# Keypad.net
KiCad netlist of a schematic drawn in Altium Designer
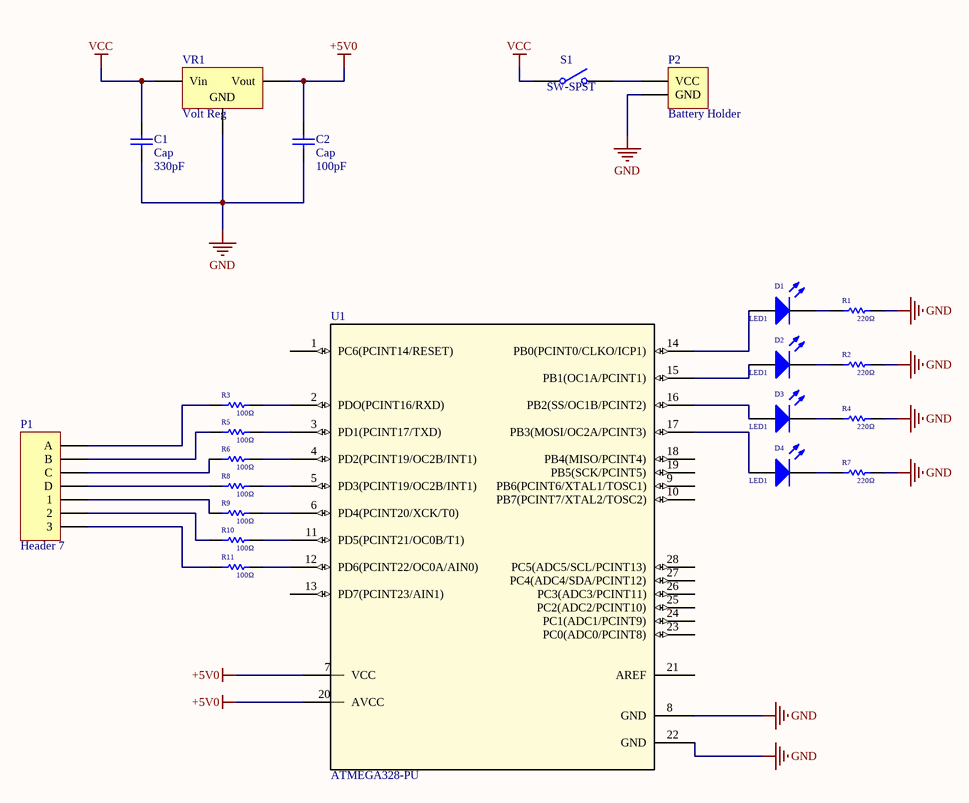
[diagram p0: Keypad.SchDoc]

(export (version "E")
  (design (tool "Eeschema 10.0.6"))
  (components
    (comp (ref "C1")
      (value "Cap")
      (footprint "RAD-0.3")
      (description "Capacitor")
      (fields (field (name "ALTIUM_VALUE") "330pF") (field (name "PUBLISHER") "Altium Limited"))
      (libsource (lib "Miscellaneous Devices") (part "Cap"))
    )
    (comp (ref "C2")
      (value "Cap")
      (footprint "RAD-0.3")
      (description "Capacitor")
      (fields (field (name "ALTIUM_VALUE") "100pF") (field (name "PUBLISHER") "Altium Limited"))
      (libsource (lib "Miscellaneous Devices") (part "Cap"))
    )
    (comp (ref "D1")
      (value "LED1")
      (footprint "LED-1")
      (description "Typical RED GaAs LED")
      (fields (field (name "PUBLISHER") "Altium Limited"))
      (libsource (lib "Miscellaneous Devices") (part "LED1"))
    )
    (comp (ref "D2")
      (value "LED1")
      (footprint "LED-1")
      (description "Typical RED GaAs LED")
      (fields (field (name "PUBLISHER") "Altium Limited"))
      (libsource (lib "Miscellaneous Devices") (part "LED1"))
    )
    (comp (ref "D3")
      (value "LED1")
      (footprint "LED-1")
      (description "Typical RED GaAs LED")
      (fields (field (name "PUBLISHER") "Altium Limited"))
      (libsource (lib "Miscellaneous Devices") (part "LED1"))
    )
    (comp (ref "D4")
      (value "LED1")
      (footprint "LED-1")
      (description "Typical RED GaAs LED")
      (fields (field (name "PUBLISHER") "Altium Limited"))
      (libsource (lib "Miscellaneous Devices") (part "LED1"))
    )
    (comp (ref "P1")
      (value "Header 7")
      (footprint "HDR1X7")
      (description "Header, 7-Pin")
      (fields (field (name "PUBLISHER") "Altium Limited"))
      (libsource (lib "Miscellaneous Connectors") (part "Header 7"))
    )
    (comp (ref "P2")
      (value "Battery Holder")
      (footprint "HDR1X2")
      (description "Header, 2-Pin")
      (fields (field (name "PUBLISHER") "Altium Limited"))
      (libsource (lib "Miscellaneous Connectors") (part "Header 2"))
    )
    (comp (ref "R1")
      (value "220Ω")
      (footprint "AXIAL-0.3")
      (description "Resistor")
      (fields (field (name "PUBLISHER") "Altium Limited"))
      (libsource (lib "Miscellaneous Devices") (part "Res1"))
    )
    (comp (ref "R2")
      (value "220Ω")
      (footprint "AXIAL-0.3")
      (description "Resistor")
      (fields (field (name "PUBLISHER") "Altium Limited"))
      (libsource (lib "Miscellaneous Devices") (part "Res1"))
    )
    (comp (ref "R3")
      (value "100Ω")
      (footprint "AXIAL-0.3")
      (description "Resistor")
      (fields (field (name "PUBLISHER") "Altium Limited"))
      (libsource (lib "Miscellaneous Devices") (part "Res1"))
    )
    (comp (ref "R4")
      (value "220Ω")
      (footprint "AXIAL-0.3")
      (description "Resistor")
      (fields (field (name "PUBLISHER") "Altium Limited"))
      (libsource (lib "Miscellaneous Devices") (part "Res1"))
    )
    (comp (ref "R5")
      (value "100Ω")
      (footprint "AXIAL-0.3")
      (description "Resistor")
      (fields (field (name "PUBLISHER") "Altium Limited"))
      (libsource (lib "Miscellaneous Devices") (part "Res1"))
    )
    (comp (ref "R6")
      (value "100Ω")
      (footprint "AXIAL-0.3")
      (description "Resistor")
      (fields (field (name "PUBLISHER") "Altium Limited"))
      (libsource (lib "Miscellaneous Devices") (part "Res1"))
    )
    (comp (ref "R7")
      (value "220Ω")
      (footprint "AXIAL-0.3")
      (description "Resistor")
      (fields (field (name "PUBLISHER") "Altium Limited"))
      (libsource (lib "Miscellaneous Devices") (part "Res1"))
    )
    (comp (ref "R8")
      (value "100Ω")
      (footprint "AXIAL-0.3")
      (description "Resistor")
      (fields (field (name "PUBLISHER") "Altium Limited"))
      (libsource (lib "Miscellaneous Devices") (part "Res1"))
    )
    (comp (ref "R9")
      (value "100Ω")
      (footprint "AXIAL-0.3")
      (description "Resistor")
      (fields (field (name "PUBLISHER") "Altium Limited"))
      (libsource (lib "Miscellaneous Devices") (part "Res1"))
    )
    (comp (ref "R10")
      (value "100Ω")
      (footprint "AXIAL-0.3")
      (description "Resistor")
      (fields (field (name "PUBLISHER") "Altium Limited"))
      (libsource (lib "Miscellaneous Devices") (part "Res1"))
    )
    (comp (ref "R11")
      (value "100Ω")
      (footprint "AXIAL-0.3")
      (description "Resistor")
      (fields (field (name "PUBLISHER") "Altium Limited"))
      (libsource (lib "Miscellaneous Devices") (part "Res1"))
    )
    (comp (ref "S1")
      (value "SW-SPST")
      (footprint "SPST-2")
      (description "Single-Pole, Single-Throw Switch")
      (fields (field (name "PUBLISHER") "Altium Limited"))
      (libsource (lib "Miscellaneous Devices") (part "SW-SPST"))
    )
    (comp (ref "U1")
      (value "ATMEGA328-PU")
      (footprint "28P3_SPDIP28_SP_MCH")
      (description "No Description Available")
      (fields (field (name "COPYRIGHT") "Copyright (C) 2018 Accelerated Designs. All rights reserved"))
      (libsource (lib "2021-05-22_12-07-40") (part "ATMEGA328-PU"))
    )
    (comp (ref "VR1")
      (value "Volt Reg")
      (footprint "D2PAK_N")
      (description "Voltage Regulator")
      (fields (field (name "PUBLISHER") "Altium Limited"))
      (libsource (lib "Miscellaneous Devices") (part "Volt Reg"))
    )
  )
  (nets
    (net (code "1") (name "+5V0") (class "Default")
      (node (ref "C2") (pin "1") (pinfunction "1_1") (pintype "passive"))
      (node (ref "U1") (pin "20") (pinfunction "AVCC_20") (pintype "power_in"))
      (node (ref "U1") (pin "7") (pinfunction "VCC_7") (pintype "power_in"))
      (node (ref "VR1") (pin "3") (pinfunction "Vout_3") (pintype "passive"))
    )
    (net (code "2") (name "GND") (class "Default")
      (node (ref "C1") (pin "2") (pinfunction "2_2") (pintype "passive"))
      (node (ref "C2") (pin "2") (pinfunction "2_2") (pintype "passive"))
      (node (ref "P2") (pin "2") (pinfunction "GND_2") (pintype "passive"))
      (node (ref "R1") (pin "2") (pinfunction "2_2") (pintype "passive"))
      (node (ref "R2") (pin "2") (pinfunction "2_2") (pintype "passive"))
      (node (ref "R4") (pin "2") (pinfunction "2_2") (pintype "passive"))
      (node (ref "R7") (pin "2") (pinfunction "2_2") (pintype "passive"))
      (node (ref "U1") (pin "22") (pinfunction "GND_22") (pintype "passive"))
      (node (ref "U1") (pin "8") (pinfunction "GND_8") (pintype "passive"))
      (node (ref "VR1") (pin "2") (pinfunction "GND_2") (pintype "passive"))
    )
    (net (code "3") (name "Net-(D1-A)") (class "Default")
      (node (ref "D1") (pin "1") (pinfunction "A_1") (pintype "passive"))
      (node (ref "U1") (pin "14") (pinfunction "PB0(PCINT0/CLKO/ICP1)_14") (pintype "bidirectional"))
    )
    (net (code "4") (name "Net-(D1-K)") (class "Default")
      (node (ref "D1") (pin "2") (pinfunction "K_2") (pintype "passive"))
      (node (ref "R1") (pin "1") (pinfunction "1_1") (pintype "passive"))
    )
    (net (code "5") (name "Net-(D2-A)") (class "Default")
      (node (ref "D2") (pin "1") (pinfunction "A_1") (pintype "passive"))
      (node (ref "U1") (pin "15") (pinfunction "PB1(OC1A/PCINT1)_15") (pintype "bidirectional"))
    )
    (net (code "6") (name "Net-(D2-K)") (class "Default")
      (node (ref "D2") (pin "2") (pinfunction "K_2") (pintype "passive"))
      (node (ref "R2") (pin "1") (pinfunction "1_1") (pintype "passive"))
    )
    (net (code "7") (name "Net-(D3-A)") (class "Default")
      (node (ref "D3") (pin "1") (pinfunction "A_1") (pintype "passive"))
      (node (ref "U1") (pin "16") (pinfunction "PB2(SS/OC1B/PCINT2)_16") (pintype "bidirectional"))
    )
    (net (code "8") (name "Net-(D3-K)") (class "Default")
      (node (ref "D3") (pin "2") (pinfunction "K_2") (pintype "passive"))
      (node (ref "R4") (pin "1") (pinfunction "1_1") (pintype "passive"))
    )
    (net (code "9") (name "Net-(D4-A)") (class "Default")
      (node (ref "D4") (pin "1") (pinfunction "A_1") (pintype "passive"))
      (node (ref "U1") (pin "17") (pinfunction "PB3(MOSI/OC2A/PCINT3)_17") (pintype "bidirectional"))
    )
    (net (code "10") (name "Net-(D4-K)") (class "Default")
      (node (ref "D4") (pin "2") (pinfunction "K_2") (pintype "passive"))
      (node (ref "R7") (pin "1") (pinfunction "1_1") (pintype "passive"))
    )
    (net (code "11") (name "Net-(P1-1)") (class "Default")
      (node (ref "P1") (pin "3") (pinfunction "1_3") (pintype "passive"))
      (node (ref "R9") (pin "1") (pinfunction "1_1") (pintype "passive"))
    )
    (net (code "12") (name "Net-(P1-3)") (class "Default")
      (node (ref "P1") (pin "1") (pinfunction "3_1") (pintype "passive"))
      (node (ref "R11") (pin "1") (pinfunction "1_1") (pintype "passive"))
    )
    (net (code "13") (name "Net-(P1-A)") (class "Default")
      (node (ref "P1") (pin "7") (pinfunction "A_7") (pintype "passive"))
      (node (ref "R3") (pin "1") (pinfunction "1_1") (pintype "passive"))
    )
    (net (code "14") (name "Net-(P1-B)") (class "Default")
      (node (ref "P1") (pin "6") (pinfunction "B_6") (pintype "passive"))
      (node (ref "R5") (pin "1") (pinfunction "1_1") (pintype "passive"))
    )
    (net (code "15") (name "Net-(P1-C)") (class "Default")
      (node (ref "P1") (pin "5") (pinfunction "C_5") (pintype "passive"))
      (node (ref "R6") (pin "1") (pinfunction "1_1") (pintype "passive"))
    )
    (net (code "16") (name "Net-(P1-D)") (class "Default")
      (node (ref "P1") (pin "4") (pinfunction "D_4") (pintype "passive"))
      (node (ref "R8") (pin "1") (pinfunction "1_1") (pintype "passive"))
    )
    (net (code "17") (name "Net-(P1-Pad2)") (class "Default")
      (node (ref "P1") (pin "2") (pinfunction "2_2") (pintype "passive"))
      (node (ref "R10") (pin "1") (pinfunction "1_1") (pintype "passive"))
    )
    (net (code "18") (name "Net-(P2-VCC)") (class "Default")
      (node (ref "P2") (pin "1") (pinfunction "VCC_1") (pintype "passive"))
      (node (ref "S1") (pin "2") (pinfunction "NO_2") (pintype "passive"))
    )
    (net (code "19") (name "Net-(U1-PD1(PCINT17{slash}TXD))") (class "Default")
      (node (ref "R5") (pin "2") (pinfunction "2_2") (pintype "passive"))
      (node (ref "U1") (pin "3") (pinfunction "PD1(PCINT17/TXD)_3") (pintype "bidirectional"))
    )
    (net (code "20") (name "Net-(U1-PD2(PCINT19{slash}OC2B{slash}INT1))") (class "Default")
      (node (ref "R6") (pin "2") (pinfunction "2_2") (pintype "passive"))
      (node (ref "U1") (pin "4") (pinfunction "PD2(PCINT19/OC2B/INT1)_4") (pintype "bidirectional"))
    )
    (net (code "21") (name "Net-(U1-PD3(PCINT19{slash}OC2B{slash}INT1))") (class "Default")
      (node (ref "R8") (pin "2") (pinfunction "2_2") (pintype "passive"))
      (node (ref "U1") (pin "5") (pinfunction "PD3(PCINT19/OC2B/INT1)_5") (pintype "bidirectional"))
    )
    (net (code "22") (name "Net-(U1-PD4(PCINT20{slash}XCK{slash}T0))") (class "Default")
      (node (ref "R9") (pin "2") (pinfunction "2_2") (pintype "passive"))
      (node (ref "U1") (pin "6") (pinfunction "PD4(PCINT20/XCK/T0)_6") (pintype "bidirectional"))
    )
    (net (code "23") (name "Net-(U1-PD5(PCINT21{slash}OC0B{slash}T1))") (class "Default")
      (node (ref "R10") (pin "2") (pinfunction "2_2") (pintype "passive"))
      (node (ref "U1") (pin "11") (pinfunction "PD5(PCINT21/OC0B/T1)_11") (pintype "bidirectional"))
    )
    (net (code "24") (name "Net-(U1-PD6(PCINT22{slash}OC0A{slash}AIN0))") (class "Default")
      (node (ref "R11") (pin "2") (pinfunction "2_2") (pintype "passive"))
      (node (ref "U1") (pin "12") (pinfunction "PD6(PCINT22/OC0A/AIN0)_12") (pintype "bidirectional"))
    )
    (net (code "25") (name "Net-(U1-PDO(PCINT16{slash}RXD))") (class "Default")
      (node (ref "R3") (pin "2") (pinfunction "2_2") (pintype "passive"))
      (node (ref "U1") (pin "2") (pinfunction "PDO(PCINT16/RXD)_2") (pintype "bidirectional"))
    )
    (net (code "26") (name "VCC") (class "Default")
      (node (ref "C1") (pin "1") (pinfunction "1_1") (pintype "passive"))
      (node (ref "S1") (pin "1") (pinfunction "COMMON_1") (pintype "passive"))
      (node (ref "VR1") (pin "1") (pinfunction "Vin_1") (pintype "passive"))
    )
    (net (code "27") (name "unconnected-(U1-AREF-Pad21)") (class "Default")
      (node (ref "U1") (pin "21") (pinfunction "AREF_21") (pintype "passive"))
    )
    (net (code "28") (name "unconnected-(U1-PB4(MISO{slash}PCINT4)-Pad18)") (class "Default")
      (node (ref "U1") (pin "18") (pinfunction "PB4(MISO/PCINT4)_18") (pintype "bidirectional"))
    )
    (net (code "29") (name "unconnected-(U1-PB5(SCK{slash}PCINT5)-Pad19)") (class "Default")
      (node (ref "U1") (pin "19") (pinfunction "PB5(SCK/PCINT5)_19") (pintype "bidirectional"))
    )
    (net (code "30") (name "unconnected-(U1-PB6(PCINT6{slash}XTAL1{slash}TOSC1)-Pad9)") (class "Default")
      (node (ref "U1") (pin "9") (pinfunction "PB6(PCINT6/XTAL1/TOSC1)_9") (pintype "bidirectional"))
    )
    (net (code "31") (name "unconnected-(U1-PB7(PCINT7{slash}XTAL2{slash}TOSC2)-Pad10)") (class "Default")
      (node (ref "U1") (pin "10") (pinfunction "PB7(PCINT7/XTAL2/TOSC2)_10") (pintype "bidirectional"))
    )
    (net (code "32") (name "unconnected-(U1-PC0(ADC0{slash}PCINT8)-Pad23)") (class "Default")
      (node (ref "U1") (pin "23") (pinfunction "PC0(ADC0/PCINT8)_23") (pintype "bidirectional"))
    )
    (net (code "33") (name "unconnected-(U1-PC1(ADC1{slash}PCINT9)-Pad24)") (class "Default")
      (node (ref "U1") (pin "24") (pinfunction "PC1(ADC1/PCINT9)_24") (pintype "bidirectional"))
    )
    (net (code "34") (name "unconnected-(U1-PC2(ADC2{slash}PCINT10)-Pad25)") (class "Default")
      (node (ref "U1") (pin "25") (pinfunction "PC2(ADC2/PCINT10)_25") (pintype "bidirectional"))
    )
    (net (code "35") (name "unconnected-(U1-PC3(ADC3{slash}PCINT11)-Pad26)") (class "Default")
      (node (ref "U1") (pin "26") (pinfunction "PC3(ADC3/PCINT11)_26") (pintype "bidirectional"))
    )
    (net (code "36") (name "unconnected-(U1-PC4(ADC4{slash}SDA{slash}PCINT12)-Pad27)") (class "Default")
      (node (ref "U1") (pin "27") (pinfunction "PC4(ADC4/SDA/PCINT12)_27") (pintype "bidirectional"))
    )
    (net (code "37") (name "unconnected-(U1-PC5(ADC5{slash}SCL{slash}PCINT13)-Pad28)") (class "Default")
      (node (ref "U1") (pin "28") (pinfunction "PC5(ADC5/SCL/PCINT13)_28") (pintype "bidirectional"))
    )
    (net (code "38") (name "unconnected-(U1-PC6(PCINT14{slash}RESET)-Pad1)") (class "Default")
      (node (ref "U1") (pin "1") (pinfunction "PC6(PCINT14/RESET)_1") (pintype "bidirectional"))
    )
    (net (code "39") (name "unconnected-(U1-PD7(PCINT23{slash}AIN1)-Pad13)") (class "Default")
      (node (ref "U1") (pin "13") (pinfunction "PD7(PCINT23/AIN1)_13") (pintype "bidirectional"))
    )
  )
)
